# RGMII_PHY.net
KiCad netlist of a schematic drawn in Altium Designer
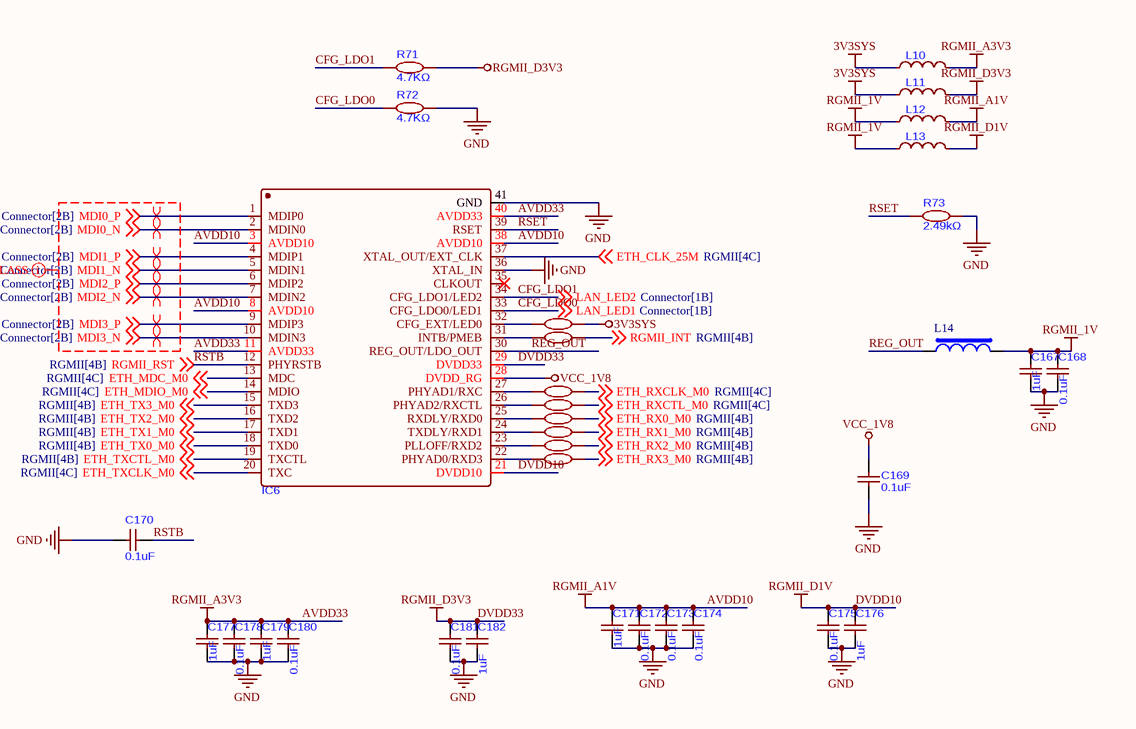
[diagram p0: RGMII_PHY.SchDoc]

(export (version "E")
  (design (tool "Eeschema 10.0.6"))
  (components
    (comp (ref "C167")
      (value "1uF")
      (footprint "C0201")
      (description "1uF ±10% 6.3V Ceramic Capacitor X5R 0201")
      (libsource (lib "Schlib1") (part "CAP_1uF-6.3V-10%-0201"))
    )
    (comp (ref "C168")
      (value "0.1uF")
      (footprint "C0201")
      (description "0.1uF ±10% 6.3V Ceramic Capacitor X5R 0201")
      (libsource (lib "Schlib1") (part "CAP_100nF-6.3V-10%-0201_1"))
    )
    (comp (ref "C169")
      (value "0.1uF")
      (footprint "C0201")
      (description "0.1uF ±10% 6.3V Ceramic Capacitor X5R 0201")
      (libsource (lib "Schlib1") (part "CAP_100nF-6.3V-10%-0201_1"))
    )
    (comp (ref "C170")
      (value "0.1uF")
      (footprint "C0201")
      (description "0.1uF ±10% 6.3V Ceramic Capacitor X5R 0201")
      (libsource (lib "Schlib1") (part "CAP_100nF-6.3V-10%-0201_1"))
    )
    (comp (ref "C171")
      (value "1uF")
      (footprint "C0201")
      (description "1uF ±10% 6.3V Ceramic Capacitor X5R 0201")
      (libsource (lib "Schlib1") (part "CAP_1uF-6.3V-10%-0201"))
    )
    (comp (ref "C172")
      (value "0.1uF")
      (footprint "C0201")
      (description "0.1uF ±10% 6.3V Ceramic Capacitor X5R 0201")
      (libsource (lib "Schlib1") (part "CAP_100nF-6.3V-10%-0201_1"))
    )
    (comp (ref "C173")
      (value "0.1uF")
      (footprint "C0201")
      (description "0.1uF ±10% 6.3V Ceramic Capacitor X5R 0201")
      (libsource (lib "Schlib1") (part "CAP_100nF-6.3V-10%-0201_1"))
    )
    (comp (ref "C174")
      (value "0.1uF")
      (footprint "C0201")
      (description "0.1uF ±10% 6.3V Ceramic Capacitor X5R 0201")
      (libsource (lib "Schlib1") (part "CAP_100nF-6.3V-10%-0201_1"))
    )
    (comp (ref "C175")
      (value "0.1uF")
      (footprint "C0201")
      (description "0.1uF ±10% 6.3V Ceramic Capacitor X5R 0201")
      (libsource (lib "Schlib1") (part "CAP_100nF-6.3V-10%-0201_1"))
    )
    (comp (ref "C176")
      (value "1uF")
      (footprint "C0201")
      (description "1uF ±10% 6.3V Ceramic Capacitor X5R 0201")
      (libsource (lib "Schlib1") (part "CAP_1uF-6.3V-10%-0201"))
    )
    (comp (ref "C177")
      (value "1uF")
      (footprint "C0201")
      (description "1uF ±10% 6.3V Ceramic Capacitor X5R 0201")
      (libsource (lib "Schlib1") (part "CAP_1uF-6.3V-10%-0201"))
    )
    (comp (ref "C178")
      (value "0.1uF")
      (footprint "C0201")
      (description "0.1uF ±10% 6.3V Ceramic Capacitor X5R 0201")
      (libsource (lib "Schlib1") (part "CAP_100nF-6.3V-10%-0201_1"))
    )
    (comp (ref "C179")
      (value "1uF")
      (footprint "C0201")
      (description "1uF ±10% 6.3V Ceramic Capacitor X5R 0201")
      (libsource (lib "Schlib1") (part "CAP_1uF-6.3V-10%-0201"))
    )
    (comp (ref "C180")
      (value "0.1uF")
      (footprint "C0201")
      (description "0.1uF ±10% 6.3V Ceramic Capacitor X5R 0201")
      (libsource (lib "Schlib1") (part "CAP_100nF-6.3V-10%-0201_1"))
    )
    (comp (ref "C181")
      (value "0.1uF")
      (footprint "C0201")
      (description "0.1uF ±10% 6.3V Ceramic Capacitor X5R 0201")
      (libsource (lib "Schlib1") (part "CAP_100nF-6.3V-10%-0201_1"))
    )
    (comp (ref "C182")
      (value "1uF")
      (footprint "C0201")
      (description "1uF ±10% 6.3V Ceramic Capacitor X5R 0201")
      (libsource (lib "Schlib1") (part "CAP_1uF-6.3V-10%-0201"))
    )
    (comp (ref "IC6")
      (value "RTL8211F-CG")
      (footprint "WQFN-40_L5.0-W5.0-P0.4-BL-EP")
      (description "Integrated 10/100/1000M Ethernet Precision Transceiver")
      (libsource (lib "Schlib1") (part "RTL8211F-CG"))
    )
    (comp (ref "L10")
      (value "FERRITE BEAD 120Ω 0201 1LN")
      (footprint "R0201")
      (description "120 Ohms @ 100MHz 1 Power Line Ferrite Bead 0201 1A 130mOhm")
      (libsource (lib "Schlib1") (part "MPZ0603S121HT000"))
    )
    (comp (ref "L11")
      (value "FERRITE BEAD 120Ω 0201 1LN")
      (footprint "R0201")
      (description "120 Ohms @ 100MHz 1 Power Line Ferrite Bead 0201 1A 130mOhm")
      (libsource (lib "Schlib1") (part "MPZ0603S121HT000"))
    )
    (comp (ref "L12")
      (value "FERRITE BEAD 120Ω 0201 1LN")
      (footprint "R0201")
      (description "120 Ohms @ 100MHz 1 Power Line Ferrite Bead 0201 1A 130mOhm")
      (libsource (lib "Schlib1") (part "MPZ0603S121HT000"))
    )
    (comp (ref "L13")
      (value "FERRITE BEAD 120Ω 0201 1LN")
      (footprint "R0201")
      (description "120 Ohms @ 100MHz 1 Power Line Ferrite Bead 0201 1A 130mOhm")
      (libsource (lib "Schlib1") (part "MPZ0603S121HT000"))
    )
    (comp (ref "L14")
      (value "PSTMAA252012-2R2MB")
      (footprint "IND_1008")
      (description "2.2uH Shielded Wirewound Inductor 4.1A 60mOhm Max 1008 (2520 Metric)")
      (fields
        (field (name "MANUFACTURER") "Murata Electronics")
        (field (name "MANUFACTURER PART NUMBER") "DFE252010P-R47M=P2")
      )
      (libsource (lib "Schlib1") (part "IND_2.2uH-4.1A-20%-1008"))
    )
    (comp (ref "R71")
      (value "4.7KΩ")
      (footprint "R0201")
      (description "RES 4.7kΩ ±1% 50mW 0201")
      (libsource (lib "Schlib1") (part "RES_4.7K-50mW-1%-0201"))
    )
    (comp (ref "R72")
      (value "4.7KΩ")
      (footprint "R0201")
      (description "RES 4.7kΩ ±1% 50mW 0201")
      (libsource (lib "Schlib1") (part "RES_4.7K-50mW-1%-0201"))
    )
    (comp (ref "R73")
      (value "2.49kΩ")
      (footprint "R0201")
      (description "RES 2.49kΩ ±1% 50mW 0201")
      (libsource (lib "Schlib1") (part "RES_2.49K-0.05W-1%-0201"))
    )
    (comp (ref "R74")
      (value "4.7KΩ")
      (footprint "R0201")
      (description "RES 4.7kΩ ±1% 50mW 0201")
      (libsource (lib "Schlib1") (part "RES_4.7K-50mW-1%-0201"))
    )
    (comp (ref "R75")
      (value "0Ω")
      (footprint "R0201")
      (description "RES 0Ω ±1% 50mW 0201")
      (libsource (lib "Schlib1") (part "RES_0OHM-50mW-1%-0201"))
    )
    (comp (ref "R76")
      (value "22Ω")
      (footprint "R0201")
      (description "RES 22Ω ±1% 50mW 0201")
      (libsource (lib "Schlib1") (part "RES_22-50mW-1%-0201"))
    )
    (comp (ref "R77")
      (value "22Ω")
      (footprint "R0201")
      (description "RES 22Ω ±1% 50mW 0201")
      (libsource (lib "Schlib1") (part "RES_22-50mW-1%-0201"))
    )
    (comp (ref "R78")
      (value "22Ω")
      (footprint "R0201")
      (description "RES 22Ω ±1% 50mW 0201")
      (libsource (lib "Schlib1") (part "RES_22-50mW-1%-0201"))
    )
    (comp (ref "R79")
      (value "22Ω")
      (footprint "R0201")
      (description "RES 22Ω ±1% 50mW 0201")
      (libsource (lib "Schlib1") (part "RES_22-50mW-1%-0201"))
    )
    (comp (ref "R80")
      (value "22Ω")
      (footprint "R0201")
      (description "RES 22Ω ±1% 50mW 0201")
      (libsource (lib "Schlib1") (part "RES_22-50mW-1%-0201"))
    )
    (comp (ref "R81")
      (value "22Ω")
      (footprint "R0201")
      (description "RES 22Ω ±1% 50mW 0201")
      (libsource (lib "Schlib1") (part "RES_22-50mW-1%-0201"))
    )
  )
  (nets
    (net (code "1") (name "/REG_OUT") (class "Default")
      (node (ref "IC6") (pin "30") (pinfunction "REG_OUT/LDO_OUT_30") (pintype "passive"))
      (node (ref "L14") (pin "1") (pinfunction "1_1") (pintype "passive"))
    )
    (net (code "2") (name "/RSET") (class "Default")
      (node (ref "IC6") (pin "39") (pinfunction "RSET_39") (pintype "passive"))
      (node (ref "R73") (pin "1") (pinfunction "1_1") (pintype "passive"))
    )
    (net (code "3") (name "3V3SYS") (class "Default")
      (node (ref "L10") (pin "1") (pinfunction "1_1") (pintype "passive"))
      (node (ref "L11") (pin "1") (pinfunction "1_1") (pintype "passive"))
      (node (ref "R74") (pin "2") (pinfunction "2_2") (pintype "passive"))
    )
    (net (code "4") (name "ETH_CLK_25M") (class "Default")
      (node (ref "IC6") (pin "37") (pinfunction "XTAL_OUT/EXT_CLK_37") (pintype "passive"))
    )
    (net (code "5") (name "ETH_MDC_M0") (class "Default")
      (node (ref "IC6") (pin "13") (pinfunction "MDC_13") (pintype "passive"))
    )
    (net (code "6") (name "ETH_MDIO_M0") (class "Default")
      (node (ref "IC6") (pin "14") (pinfunction "MDIO_14") (pintype "passive"))
    )
    (net (code "7") (name "ETH_RX0_M0") (class "Default")
      (node (ref "R78") (pin "2") (pinfunction "2_2") (pintype "passive"))
    )
    (net (code "8") (name "ETH_RX1_M0") (class "Default")
      (node (ref "R79") (pin "2") (pinfunction "2_2") (pintype "passive"))
    )
    (net (code "9") (name "ETH_RX2_M0") (class "Default")
      (node (ref "R80") (pin "2") (pinfunction "2_2") (pintype "passive"))
    )
    (net (code "10") (name "ETH_RX3_M0") (class "Default")
      (node (ref "R81") (pin "2") (pinfunction "2_2") (pintype "passive"))
    )
    (net (code "11") (name "ETH_RXCLK_M0") (class "Default")
      (node (ref "R76") (pin "2") (pinfunction "2_2") (pintype "passive"))
    )
    (net (code "12") (name "ETH_RXCTL_M0") (class "Default")
      (node (ref "R77") (pin "2") (pinfunction "2_2") (pintype "passive"))
    )
    (net (code "13") (name "ETH_TX0_M0") (class "Default")
      (node (ref "IC6") (pin "18") (pinfunction "TXD0_18") (pintype "passive"))
    )
    (net (code "14") (name "ETH_TX1_M0") (class "Default")
      (node (ref "IC6") (pin "17") (pinfunction "TXD1_17") (pintype "passive"))
    )
    (net (code "15") (name "ETH_TX2_M0") (class "Default")
      (node (ref "IC6") (pin "16") (pinfunction "TXD2_16") (pintype "passive"))
    )
    (net (code "16") (name "ETH_TX3_M0") (class "Default")
      (node (ref "IC6") (pin "15") (pinfunction "TXD3_15") (pintype "passive"))
    )
    (net (code "17") (name "ETH_TXCLK_M0") (class "Default")
      (node (ref "IC6") (pin "20") (pinfunction "TXC_20") (pintype "passive"))
    )
    (net (code "18") (name "ETH_TXCTL_M0") (class "Default")
      (node (ref "IC6") (pin "19") (pinfunction "TXCTL_19") (pintype "passive"))
    )
    (net (code "19") (name "GND") (class "Default")
      (node (ref "C167") (pin "1") (pinfunction "1_1") (pintype "passive"))
      (node (ref "C168") (pin "1") (pinfunction "1_1") (pintype "passive"))
      (node (ref "C169") (pin "1") (pinfunction "1_1") (pintype "passive"))
      (node (ref "C170") (pin "2") (pinfunction "2_2") (pintype "passive"))
      (node (ref "C171") (pin "1") (pinfunction "1_1") (pintype "passive"))
      (node (ref "C172") (pin "1") (pinfunction "1_1") (pintype "passive"))
      (node (ref "C173") (pin "1") (pinfunction "1_1") (pintype "passive"))
      (node (ref "C174") (pin "1") (pinfunction "1_1") (pintype "passive"))
      (node (ref "C175") (pin "1") (pinfunction "1_1") (pintype "passive"))
      (node (ref "C176") (pin "1") (pinfunction "1_1") (pintype "passive"))
      (node (ref "C177") (pin "1") (pinfunction "1_1") (pintype "passive"))
      (node (ref "C178") (pin "1") (pinfunction "1_1") (pintype "passive"))
      (node (ref "C179") (pin "1") (pinfunction "1_1") (pintype "passive"))
      (node (ref "C180") (pin "1") (pinfunction "1_1") (pintype "passive"))
      (node (ref "C181") (pin "1") (pinfunction "1_1") (pintype "passive"))
      (node (ref "C182") (pin "1") (pinfunction "1_1") (pintype "passive"))
      (node (ref "IC6") (pin "36") (pinfunction "XTAL_IN_36") (pintype "passive"))
      (node (ref "IC6") (pin "41") (pinfunction "GND_41") (pintype "passive"))
      (node (ref "R72") (pin "1") (pinfunction "1_1") (pintype "passive"))
      (node (ref "R73") (pin "2") (pinfunction "2_2") (pintype "passive"))
    )
    (net (code "20") (name "LAN_LED1") (class "Default")
      (node (ref "IC6") (pin "33") (pinfunction "CFG_LDO0/LED1_33") (pintype "passive"))
      (node (ref "R72") (pin "2") (pinfunction "2_2") (pintype "passive"))
    )
    (net (code "21") (name "LAN_LED2") (class "Default")
      (node (ref "IC6") (pin "34") (pinfunction "CFG_LDO1/LED2_34") (pintype "passive"))
      (node (ref "R71") (pin "2") (pinfunction "2_2") (pintype "passive"))
    )
    (net (code "22") (name "MDI0_N") (class "Default")
      (node (ref "IC6") (pin "2") (pinfunction "MDIN0_2") (pintype "passive"))
    )
    (net (code "23") (name "MDI0_P") (class "Default")
      (node (ref "IC6") (pin "1") (pinfunction "MDIP0_1") (pintype "passive"))
    )
    (net (code "24") (name "MDI1_N") (class "Default")
      (node (ref "IC6") (pin "5") (pinfunction "MDIN1_5") (pintype "passive"))
    )
    (net (code "25") (name "MDI1_P") (class "Default")
      (node (ref "IC6") (pin "4") (pinfunction "MDIP1_4") (pintype "passive"))
    )
    (net (code "26") (name "MDI2_N") (class "Default")
      (node (ref "IC6") (pin "7") (pinfunction "MDIN2_7") (pintype "passive"))
    )
    (net (code "27") (name "MDI2_P") (class "Default")
      (node (ref "IC6") (pin "6") (pinfunction "MDIP2_6") (pintype "passive"))
    )
    (net (code "28") (name "MDI3_N") (class "Default")
      (node (ref "IC6") (pin "10") (pinfunction "MDIN3_10") (pintype "passive"))
    )
    (net (code "29") (name "MDI3_P") (class "Default")
      (node (ref "IC6") (pin "9") (pinfunction "MDIP3_9") (pintype "passive"))
    )
    (net (code "30") (name "Net-(IC6-CFG_EXT{slash}LED0)") (class "Default")
      (node (ref "IC6") (pin "32") (pinfunction "CFG_EXT/LED0_32") (pintype "passive"))
      (node (ref "R74") (pin "1") (pinfunction "1_1") (pintype "passive"))
    )
    (net (code "31") (name "Net-(IC6-INTB{slash}PMEB)") (class "Default")
      (node (ref "IC6") (pin "31") (pinfunction "INTB/PMEB_31") (pintype "passive"))
      (node (ref "R75") (pin "1") (pinfunction "1_1") (pintype "passive"))
    )
    (net (code "32") (name "Net-(IC6-PHYAD0{slash}RXD3)") (class "Default")
      (node (ref "IC6") (pin "22") (pinfunction "PHYAD0/RXD3_22") (pintype "passive"))
      (node (ref "R81") (pin "1") (pinfunction "1_1") (pintype "passive"))
    )
    (net (code "33") (name "Net-(IC6-PHYAD1{slash}RXC)") (class "Default")
      (node (ref "IC6") (pin "27") (pinfunction "PHYAD1/RXC_27") (pintype "passive"))
      (node (ref "R76") (pin "1") (pinfunction "1_1") (pintype "passive"))
    )
    (net (code "34") (name "Net-(IC6-PHYAD2{slash}RXCTL)") (class "Default")
      (node (ref "IC6") (pin "26") (pinfunction "PHYAD2/RXCTL_26") (pintype "passive"))
      (node (ref "R77") (pin "1") (pinfunction "1_1") (pintype "passive"))
    )
    (net (code "35") (name "Net-(IC6-PLLOFF{slash}RXD2)") (class "Default")
      (node (ref "IC6") (pin "23") (pinfunction "PLLOFF/RXD2_23") (pintype "passive"))
      (node (ref "R80") (pin "1") (pinfunction "1_1") (pintype "passive"))
    )
    (net (code "36") (name "Net-(IC6-RXDLY{slash}RXD0)") (class "Default")
      (node (ref "IC6") (pin "25") (pinfunction "RXDLY/RXD0_25") (pintype "passive"))
      (node (ref "R78") (pin "1") (pinfunction "1_1") (pintype "passive"))
    )
    (net (code "37") (name "Net-(IC6-TXDLY{slash}RXD1)") (class "Default")
      (node (ref "IC6") (pin "24") (pinfunction "TXDLY/RXD1_24") (pintype "passive"))
      (node (ref "R79") (pin "1") (pinfunction "1_1") (pintype "passive"))
    )
    (net (code "38") (name "RGMII_1V") (class "Default")
      (node (ref "C167") (pin "2") (pinfunction "2_2") (pintype "passive"))
      (node (ref "C168") (pin "2") (pinfunction "2_2") (pintype "passive"))
      (node (ref "L12") (pin "1") (pinfunction "1_1") (pintype "passive"))
      (node (ref "L13") (pin "1") (pinfunction "1_1") (pintype "passive"))
      (node (ref "L14") (pin "2") (pinfunction "2_2") (pintype "passive"))
    )
    (net (code "39") (name "RGMII_A1V") (class "Default")
      (node (ref "C171") (pin "2") (pinfunction "2_2") (pintype "passive"))
      (node (ref "C172") (pin "2") (pinfunction "2_2") (pintype "passive"))
      (node (ref "C173") (pin "2") (pinfunction "2_2") (pintype "passive"))
      (node (ref "C174") (pin "2") (pinfunction "2_2") (pintype "passive"))
      (node (ref "IC6") (pin "3") (pinfunction "AVDD10_3") (pintype "passive"))
      (node (ref "IC6") (pin "38") (pinfunction "AVDD10_38") (pintype "passive"))
      (node (ref "IC6") (pin "8") (pinfunction "AVDD10_8") (pintype "passive"))
      (node (ref "L12") (pin "2") (pinfunction "2_2") (pintype "passive"))
    )
    (net (code "40") (name "RGMII_A3V3") (class "Default")
      (node (ref "C177") (pin "2") (pinfunction "2_2") (pintype "passive"))
      (node (ref "C178") (pin "2") (pinfunction "2_2") (pintype "passive"))
      (node (ref "C179") (pin "2") (pinfunction "2_2") (pintype "passive"))
      (node (ref "C180") (pin "2") (pinfunction "2_2") (pintype "passive"))
      (node (ref "IC6") (pin "11") (pinfunction "AVDD33_11") (pintype "passive"))
      (node (ref "IC6") (pin "40") (pinfunction "AVDD33_40") (pintype "passive"))
      (node (ref "L10") (pin "2") (pinfunction "2_2") (pintype "passive"))
    )
    (net (code "41") (name "RGMII_D1V") (class "Default")
      (node (ref "C175") (pin "2") (pinfunction "2_2") (pintype "passive"))
      (node (ref "C176") (pin "2") (pinfunction "2_2") (pintype "passive"))
      (node (ref "IC6") (pin "21") (pinfunction "DVDD10_21") (pintype "passive"))
      (node (ref "L13") (pin "2") (pinfunction "2_2") (pintype "passive"))
    )
    (net (code "42") (name "RGMII_D3V3") (class "Default")
      (node (ref "C181") (pin "2") (pinfunction "2_2") (pintype "passive"))
      (node (ref "C182") (pin "2") (pinfunction "2_2") (pintype "passive"))
      (node (ref "IC6") (pin "29") (pinfunction "DVDD33_29") (pintype "passive"))
      (node (ref "L11") (pin "2") (pinfunction "2_2") (pintype "passive"))
      (node (ref "R71") (pin "1") (pinfunction "1_1") (pintype "passive"))
    )
    (net (code "43") (name "RGMII_INT") (class "Default")
      (node (ref "R75") (pin "2") (pinfunction "2_2") (pintype "passive"))
    )
    (net (code "44") (name "RGMII_RST") (class "Default")
      (node (ref "C170") (pin "1") (pinfunction "1_1") (pintype "passive"))
      (node (ref "IC6") (pin "12") (pinfunction "PHYRSTB_12") (pintype "passive"))
    )
    (net (code "45") (name "VCC_1V8") (class "Default")
      (node (ref "C169") (pin "2") (pinfunction "2_2") (pintype "passive"))
      (node (ref "IC6") (pin "28") (pinfunction "DVDD_RG_28") (pintype "passive"))
    )
    (net (code "46") (name "unconnected-(IC6-CLKOUT-Pad35)") (class "Default")
      (node (ref "IC6") (pin "35") (pinfunction "CLKOUT_35") (pintype "passive+no_connect"))
    )
  )
)
